# multi.net
KiCad netlist of a schematic drawn in EAGLE
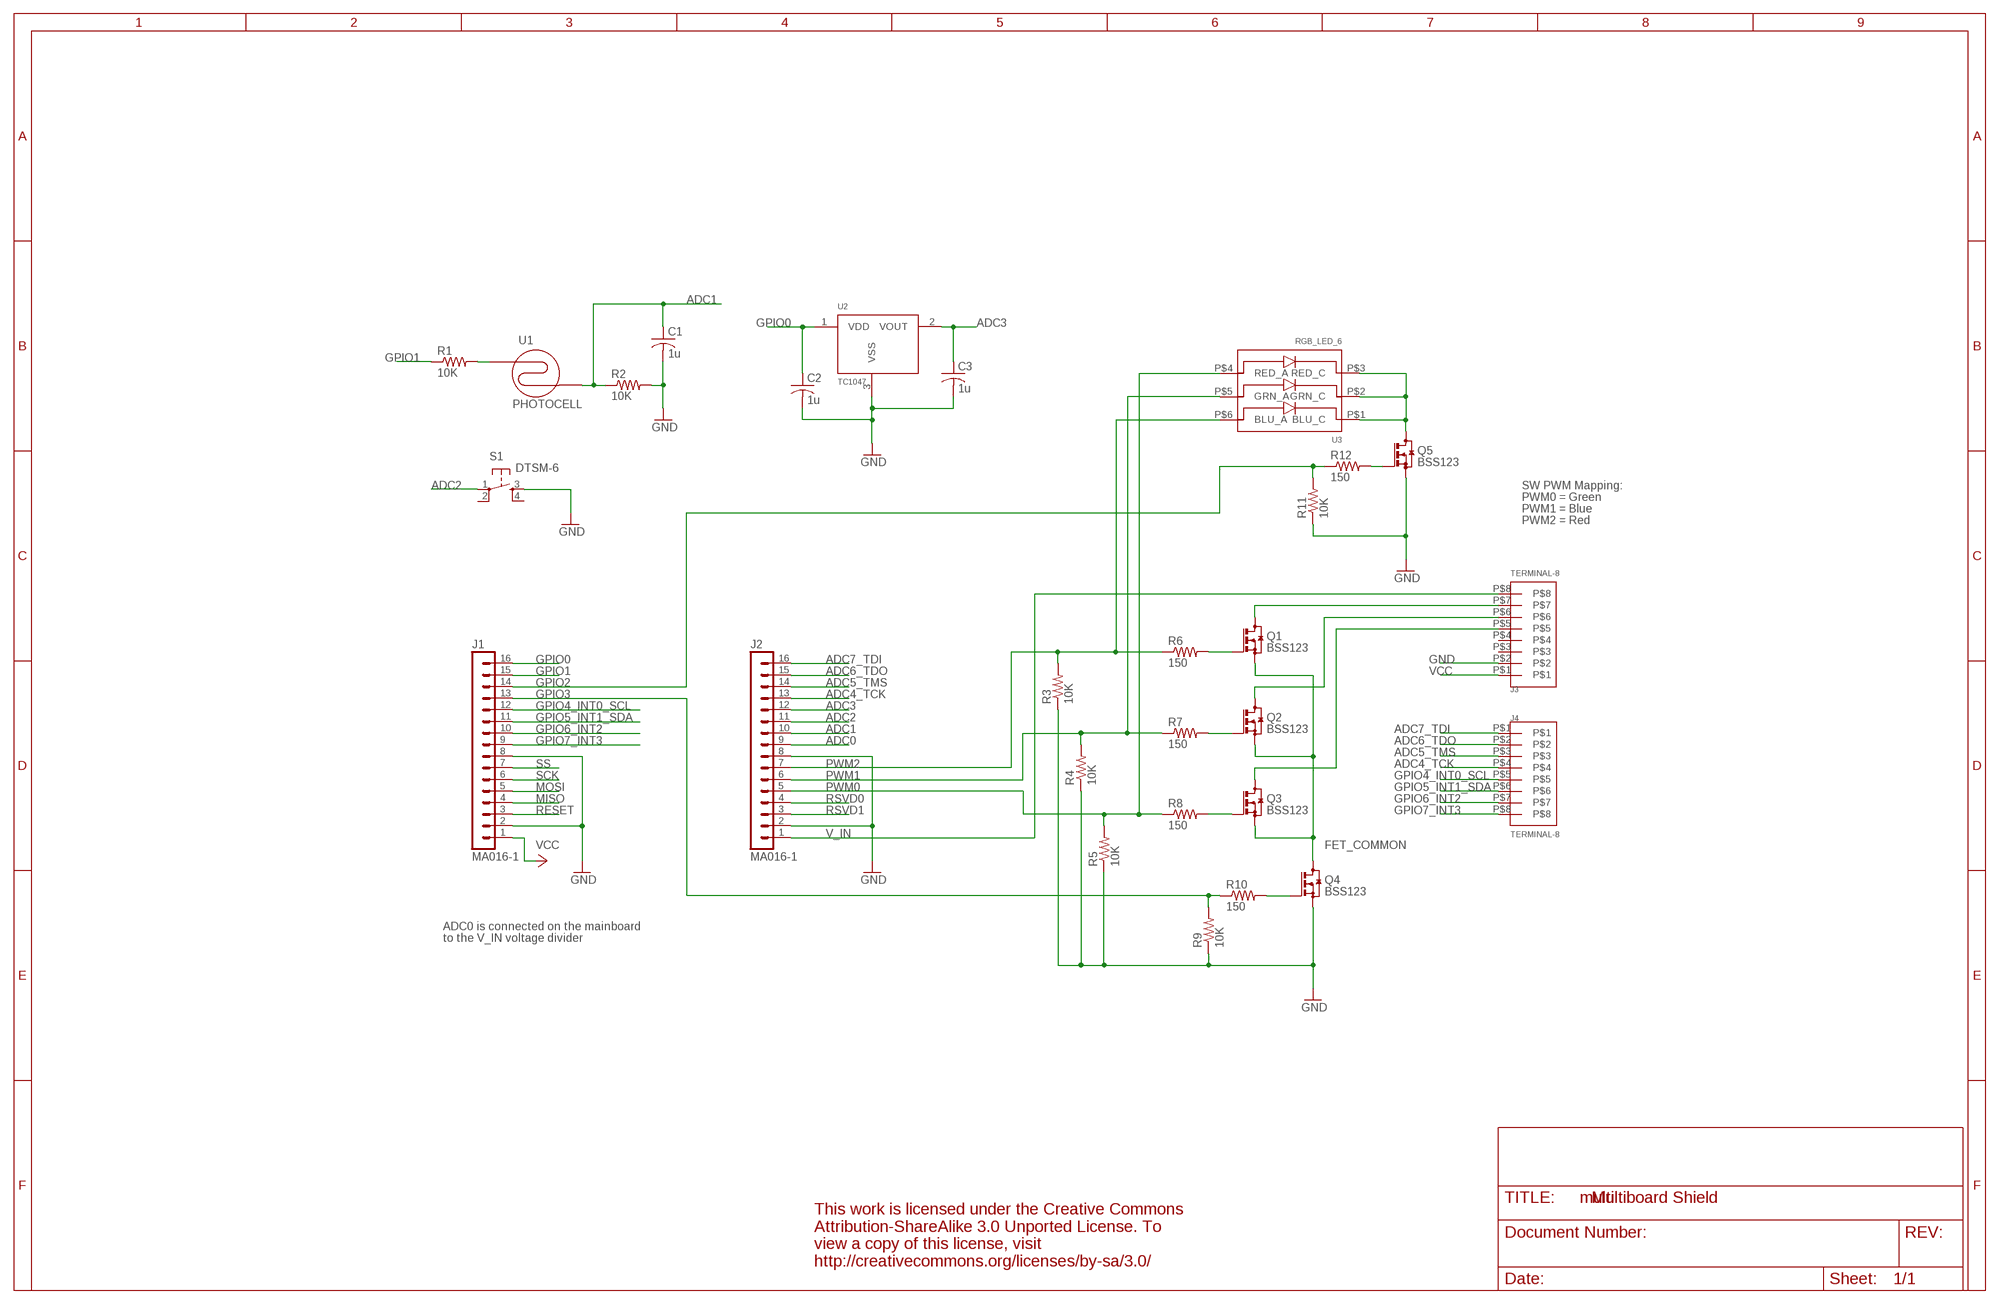
[diagram p0: schematic, sheet 1]

(export (version "E")
  (design (tool "Eeschema 10.0.6"))
  (components
    (comp (ref "C1")
      (value "1u")
      (footprint "eagle-import:C0603K")
      (libsource (lib "eagle-import") (part "C-USC0603K"))
    )
    (comp (ref "C2")
      (value "1u")
      (footprint "eagle-import:C0603K")
      (libsource (lib "eagle-import") (part "C-USC0603K"))
    )
    (comp (ref "C3")
      (value "1u")
      (footprint "eagle-import:C0603K")
      (libsource (lib "eagle-import") (part "C-USC0603K"))
    )
    (comp (ref "J1")
      (value "MA016-1")
      (footprint "eagle-import:MA016-1")
      (libsource (lib "eagle-import") (part "MA016-1"))
    )
    (comp (ref "J2")
      (value "MA016-1")
      (footprint "eagle-import:MA016-1")
      (libsource (lib "eagle-import") (part "MA016-1"))
    )
    (comp (ref "J3")
      (value "TERMINAL-8")
      (footprint "eagle-import:TERMINAL-8")
      (libsource (lib "eagle-import") (part "TERMINAL-8"))
    )
    (comp (ref "J4")
      (value "TERMINAL-8")
      (footprint "eagle-import:TERMINAL-8")
      (libsource (lib "eagle-import") (part "TERMINAL-8"))
    )
    (comp (ref "Q1")
      (value "BSS123")
      (footprint "eagle-import:SOT23")
      (libsource (lib "eagle-import") (part "BSS123"))
    )
    (comp (ref "Q2")
      (value "BSS123")
      (footprint "eagle-import:SOT23")
      (libsource (lib "eagle-import") (part "BSS123"))
    )
    (comp (ref "Q3")
      (value "BSS123")
      (footprint "eagle-import:SOT23")
      (libsource (lib "eagle-import") (part "BSS123"))
    )
    (comp (ref "Q4")
      (value "BSS123")
      (footprint "eagle-import:SOT23")
      (libsource (lib "eagle-import") (part "BSS123"))
    )
    (comp (ref "Q5")
      (value "BSS123")
      (footprint "eagle-import:SOT23")
      (libsource (lib "eagle-import") (part "BSS123"))
    )
    (comp (ref "R1")
      (value "10K")
      (footprint "eagle-import:R0603")
      (libsource (lib "eagle-import") (part "R-US_R0603"))
    )
    (comp (ref "R2")
      (value "10K")
      (footprint "eagle-import:R0603")
      (libsource (lib "eagle-import") (part "R-US_R0603"))
    )
    (comp (ref "R3")
      (value "10K")
      (footprint "eagle-import:R0603")
      (libsource (lib "eagle-import") (part "R-US_R0603"))
    )
    (comp (ref "R4")
      (value "10K")
      (footprint "eagle-import:R0603")
      (libsource (lib "eagle-import") (part "R-US_R0603"))
    )
    (comp (ref "R5")
      (value "10K")
      (footprint "eagle-import:R0603")
      (libsource (lib "eagle-import") (part "R-US_R0603"))
    )
    (comp (ref "R6")
      (value "150")
      (footprint "eagle-import:R0603")
      (libsource (lib "eagle-import") (part "R-US_R0603"))
    )
    (comp (ref "R7")
      (value "150")
      (footprint "eagle-import:R0603")
      (libsource (lib "eagle-import") (part "R-US_R0603"))
    )
    (comp (ref "R8")
      (value "150")
      (footprint "eagle-import:R0603")
      (libsource (lib "eagle-import") (part "R-US_R0603"))
    )
    (comp (ref "R9")
      (value "10K")
      (footprint "eagle-import:R0603")
      (libsource (lib "eagle-import") (part "R-US_R0603"))
    )
    (comp (ref "R10")
      (value "150")
      (footprint "eagle-import:R0603")
      (libsource (lib "eagle-import") (part "R-US_R0603"))
    )
    (comp (ref "R11")
      (value "10K")
      (footprint "eagle-import:R0603")
      (libsource (lib "eagle-import") (part "R-US_R0603"))
    )
    (comp (ref "R12")
      (value "150")
      (footprint "eagle-import:R0603")
      (libsource (lib "eagle-import") (part "R-US_R0603"))
    )
    (comp (ref "S1")
      (value "DTSM-6")
      (footprint "eagle-import:DTSM-6")
      (libsource (lib "eagle-import") (part "DTSM-6"))
    )
    (comp (ref "U1")
      (value "PHOTOCELL")
      (footprint "eagle-import:PHOTOCELL")
      (libsource (lib "eagle-import") (part "PHOTOCELL"))
    )
    (comp (ref "U2")
      (value "TC1047")
      (footprint "eagle-import:SOT23")
      (libsource (lib "eagle-import") (part "TC1047"))
    )
    (comp (ref "U3")
      (value "RGB_LED_6")
      (footprint "eagle-import:PLCC6")
      (libsource (lib "eagle-import") (part "RGB_LED_6"))
    )
  )
  (nets
    (net (code "1") (name "/ADC0") (class "Default")
      (node (ref "J2") (pin "9") (pinfunction "9_9") (pintype "passive"))
    )
    (net (code "2") (name "/ADC1") (class "Default")
      (node (ref "C1") (pin "1") (pinfunction "1_1") (pintype "passive"))
      (node (ref "J2") (pin "10") (pinfunction "10_10") (pintype "passive"))
      (node (ref "R2") (pin "1") (pinfunction "1_1") (pintype "passive"))
      (node (ref "U1") (pin "P$2") (pinfunction "P$2_P$2") (pintype "bidirectional"))
    )
    (net (code "3") (name "/ADC2") (class "Default")
      (node (ref "J2") (pin "11") (pinfunction "11_11") (pintype "passive"))
      (node (ref "S1") (pin "1") (pinfunction "1_1") (pintype "passive"))
    )
    (net (code "4") (name "/ADC3") (class "Default")
      (node (ref "C3") (pin "1") (pinfunction "1_1") (pintype "passive"))
      (node (ref "J2") (pin "12") (pinfunction "12_12") (pintype "passive"))
      (node (ref "U2") (pin "2") (pinfunction "VOUT_2") (pintype "bidirectional"))
    )
    (net (code "5") (name "/ADC4_TCK") (class "Default")
      (node (ref "J2") (pin "13") (pinfunction "13_13") (pintype "passive"))
      (node (ref "J4") (pin "P$4") (pinfunction "P$4_P$4") (pintype "bidirectional"))
    )
    (net (code "6") (name "/ADC5_TMS") (class "Default")
      (node (ref "J2") (pin "14") (pinfunction "14_14") (pintype "passive"))
      (node (ref "J4") (pin "P$3") (pinfunction "P$3_P$3") (pintype "bidirectional"))
    )
    (net (code "7") (name "/ADC6_TDO") (class "Default")
      (node (ref "J2") (pin "15") (pinfunction "15_15") (pintype "passive"))
      (node (ref "J4") (pin "P$2") (pinfunction "P$2_P$2") (pintype "bidirectional"))
    )
    (net (code "8") (name "/ADC7_TDI") (class "Default")
      (node (ref "J2") (pin "16") (pinfunction "16_16") (pintype "passive"))
      (node (ref "J4") (pin "P$1") (pinfunction "P$1_P$1") (pintype "bidirectional"))
    )
    (net (code "9") (name "/FET_COMMON") (class "Default")
      (node (ref "Q1") (pin "2") (pinfunction "S_2") (pintype "passive"))
      (node (ref "Q2") (pin "2") (pinfunction "S_2") (pintype "passive"))
      (node (ref "Q3") (pin "2") (pinfunction "S_2") (pintype "passive"))
      (node (ref "Q4") (pin "3") (pinfunction "D_3") (pintype "passive"))
    )
    (net (code "10") (name "/GPIO0") (class "Default")
      (node (ref "C2") (pin "1") (pinfunction "1_1") (pintype "passive"))
      (node (ref "J1") (pin "16") (pinfunction "16_16") (pintype "passive"))
      (node (ref "U2") (pin "1") (pinfunction "VDD_1") (pintype "bidirectional"))
    )
    (net (code "11") (name "/GPIO1") (class "Default")
      (node (ref "J1") (pin "15") (pinfunction "15_15") (pintype "passive"))
      (node (ref "R1") (pin "1") (pinfunction "1_1") (pintype "passive"))
    )
    (net (code "12") (name "/GPIO2") (class "Default")
      (node (ref "J1") (pin "14") (pinfunction "14_14") (pintype "passive"))
      (node (ref "R11") (pin "2") (pinfunction "2_2") (pintype "passive"))
      (node (ref "R12") (pin "1") (pinfunction "1_1") (pintype "passive"))
    )
    (net (code "13") (name "/GPIO3") (class "Default")
      (node (ref "J1") (pin "13") (pinfunction "13_13") (pintype "passive"))
      (node (ref "R10") (pin "1") (pinfunction "1_1") (pintype "passive"))
      (node (ref "R9") (pin "2") (pinfunction "2_2") (pintype "passive"))
    )
    (net (code "14") (name "/GPIO4_INT0_SCL") (class "Default")
      (node (ref "J1") (pin "12") (pinfunction "12_12") (pintype "passive"))
      (node (ref "J4") (pin "P$5") (pinfunction "P$5_P$5") (pintype "bidirectional"))
    )
    (net (code "15") (name "/GPIO5_INT1_SDA") (class "Default")
      (node (ref "J1") (pin "11") (pinfunction "11_11") (pintype "passive"))
      (node (ref "J4") (pin "P$6") (pinfunction "P$6_P$6") (pintype "bidirectional"))
    )
    (net (code "16") (name "/GPIO6_INT2") (class "Default")
      (node (ref "J1") (pin "10") (pinfunction "10_10") (pintype "passive"))
      (node (ref "J4") (pin "P$7") (pinfunction "P$7_P$7") (pintype "bidirectional"))
    )
    (net (code "17") (name "/GPIO7_INT3") (class "Default")
      (node (ref "J1") (pin "9") (pinfunction "9_9") (pintype "passive"))
      (node (ref "J4") (pin "P$8") (pinfunction "P$8_P$8") (pintype "bidirectional"))
    )
    (net (code "18") (name "/MISO") (class "Default")
      (node (ref "J1") (pin "4") (pinfunction "4_4") (pintype "passive"))
    )
    (net (code "19") (name "/MOSI") (class "Default")
      (node (ref "J1") (pin "5") (pinfunction "5_5") (pintype "passive"))
    )
    (net (code "20") (name "/PWM0") (class "Default")
      (node (ref "J2") (pin "5") (pinfunction "5_5") (pintype "passive"))
      (node (ref "R5") (pin "2") (pinfunction "2_2") (pintype "passive"))
      (node (ref "R8") (pin "1") (pinfunction "1_1") (pintype "passive"))
      (node (ref "U3") (pin "P$4") (pinfunction "RED_A_P$4") (pintype "bidirectional"))
    )
    (net (code "21") (name "/PWM1") (class "Default")
      (node (ref "J2") (pin "6") (pinfunction "6_6") (pintype "passive"))
      (node (ref "R4") (pin "2") (pinfunction "2_2") (pintype "passive"))
      (node (ref "R7") (pin "1") (pinfunction "1_1") (pintype "passive"))
      (node (ref "U3") (pin "P$5") (pinfunction "GRN_A_P$5") (pintype "bidirectional"))
    )
    (net (code "22") (name "/PWM2") (class "Default")
      (node (ref "J2") (pin "7") (pinfunction "7_7") (pintype "passive"))
      (node (ref "R3") (pin "2") (pinfunction "2_2") (pintype "passive"))
      (node (ref "R6") (pin "1") (pinfunction "1_1") (pintype "passive"))
      (node (ref "U3") (pin "P$6") (pinfunction "BLU_A_P$6") (pintype "bidirectional"))
    )
    (net (code "23") (name "/RESET") (class "Default")
      (node (ref "J1") (pin "3") (pinfunction "3_3") (pintype "passive"))
    )
    (net (code "24") (name "/RSVD0") (class "Default")
      (node (ref "J2") (pin "4") (pinfunction "4_4") (pintype "passive"))
    )
    (net (code "25") (name "/RSVD1") (class "Default")
      (node (ref "J2") (pin "3") (pinfunction "3_3") (pintype "passive"))
    )
    (net (code "26") (name "/SCK") (class "Default")
      (node (ref "J1") (pin "6") (pinfunction "6_6") (pintype "passive"))
    )
    (net (code "27") (name "/SS") (class "Default")
      (node (ref "J1") (pin "7") (pinfunction "7_7") (pintype "passive"))
    )
    (net (code "28") (name "/V_IN") (class "Default")
      (node (ref "J2") (pin "1") (pinfunction "1_1") (pintype "passive"))
      (node (ref "J3") (pin "P$8") (pinfunction "P$8_P$8") (pintype "bidirectional"))
    )
    (net (code "29") (name "GND") (class "Default")
      (node (ref "C1") (pin "2") (pinfunction "2_2") (pintype "passive"))
      (node (ref "C2") (pin "2") (pinfunction "2_2") (pintype "passive"))
      (node (ref "C3") (pin "2") (pinfunction "2_2") (pintype "passive"))
      (node (ref "J1") (pin "2") (pinfunction "2_2") (pintype "passive"))
      (node (ref "J1") (pin "8") (pinfunction "8_8") (pintype "passive"))
      (node (ref "J2") (pin "2") (pinfunction "2_2") (pintype "passive"))
      (node (ref "J2") (pin "8") (pinfunction "8_8") (pintype "passive"))
      (node (ref "J3") (pin "P$2") (pinfunction "P$2_P$2") (pintype "bidirectional"))
      (node (ref "Q4") (pin "2") (pinfunction "S_2") (pintype "passive"))
      (node (ref "Q5") (pin "2") (pinfunction "S_2") (pintype "passive"))
      (node (ref "R11") (pin "1") (pinfunction "1_1") (pintype "passive"))
      (node (ref "R2") (pin "2") (pinfunction "2_2") (pintype "passive"))
      (node (ref "R3") (pin "1") (pinfunction "1_1") (pintype "passive"))
      (node (ref "R4") (pin "1") (pinfunction "1_1") (pintype "passive"))
      (node (ref "R5") (pin "1") (pinfunction "1_1") (pintype "passive"))
      (node (ref "R9") (pin "1") (pinfunction "1_1") (pintype "passive"))
      (node (ref "S1") (pin "3") (pinfunction "3_3") (pintype "passive"))
      (node (ref "U2") (pin "3") (pinfunction "VSS_3") (pintype "bidirectional"))
    )
    (net (code "30") (name "Net-(Q1-D)") (class "Default")
      (node (ref "J3") (pin "P$7") (pinfunction "P$7_P$7") (pintype "bidirectional"))
      (node (ref "Q1") (pin "3") (pinfunction "D_3") (pintype "passive"))
    )
    (net (code "31") (name "Net-(Q1-G)") (class "Default")
      (node (ref "Q1") (pin "1") (pinfunction "G_1") (pintype "passive"))
      (node (ref "R6") (pin "2") (pinfunction "2_2") (pintype "passive"))
    )
    (net (code "32") (name "Net-(Q2-D)") (class "Default")
      (node (ref "J3") (pin "P$6") (pinfunction "P$6_P$6") (pintype "bidirectional"))
      (node (ref "Q2") (pin "3") (pinfunction "D_3") (pintype "passive"))
    )
    (net (code "33") (name "Net-(Q2-G)") (class "Default")
      (node (ref "Q2") (pin "1") (pinfunction "G_1") (pintype "passive"))
      (node (ref "R7") (pin "2") (pinfunction "2_2") (pintype "passive"))
    )
    (net (code "34") (name "Net-(Q3-D)") (class "Default")
      (node (ref "J3") (pin "P$5") (pinfunction "P$5_P$5") (pintype "bidirectional"))
      (node (ref "Q3") (pin "3") (pinfunction "D_3") (pintype "passive"))
    )
    (net (code "35") (name "Net-(Q3-G)") (class "Default")
      (node (ref "Q3") (pin "1") (pinfunction "G_1") (pintype "passive"))
      (node (ref "R8") (pin "2") (pinfunction "2_2") (pintype "passive"))
    )
    (net (code "36") (name "Net-(Q4-G)") (class "Default")
      (node (ref "Q4") (pin "1") (pinfunction "G_1") (pintype "passive"))
      (node (ref "R10") (pin "2") (pinfunction "2_2") (pintype "passive"))
    )
    (net (code "37") (name "Net-(Q5-D)") (class "Default")
      (node (ref "Q5") (pin "3") (pinfunction "D_3") (pintype "passive"))
      (node (ref "U3") (pin "P$1") (pinfunction "BLU_C_P$1") (pintype "bidirectional"))
      (node (ref "U3") (pin "P$2") (pinfunction "GRN_C_P$2") (pintype "bidirectional"))
      (node (ref "U3") (pin "P$3") (pinfunction "RED_C_P$3") (pintype "bidirectional"))
    )
    (net (code "38") (name "Net-(Q5-G)") (class "Default")
      (node (ref "Q5") (pin "1") (pinfunction "G_1") (pintype "passive"))
      (node (ref "R12") (pin "2") (pinfunction "2_2") (pintype "passive"))
    )
    (net (code "39") (name "Net-(R1-Pad2)") (class "Default")
      (node (ref "R1") (pin "2") (pinfunction "2_2") (pintype "passive"))
      (node (ref "U1") (pin "P$1") (pinfunction "P$1_P$1") (pintype "bidirectional"))
    )
    (net (code "40") (name "VCC") (class "Default")
      (node (ref "J1") (pin "1") (pinfunction "1_1") (pintype "passive"))
      (node (ref "J3") (pin "P$1") (pinfunction "P$1_P$1") (pintype "bidirectional"))
    )
    (net (code "41") (name "unconnected-(J3-PadP$3)") (class "Default")
      (node (ref "J3") (pin "P$3") (pinfunction "P$3_P$3") (pintype "bidirectional"))
    )
    (net (code "42") (name "unconnected-(J3-PadP$4)") (class "Default")
      (node (ref "J3") (pin "P$4") (pinfunction "P$4_P$4") (pintype "bidirectional"))
    )
    (net (code "43") (name "unconnected-(S1-Pad2)") (class "Default")
      (node (ref "S1") (pin "2") (pinfunction "2_2") (pintype "passive"))
    )
    (net (code "44") (name "unconnected-(S1-Pad4)") (class "Default")
      (node (ref "S1") (pin "4") (pinfunction "4_4") (pintype "passive"))
    )
  )
)
